# Shutdown_Nodes.net
KiCad netlist of a schematic drawn in Altium Designer
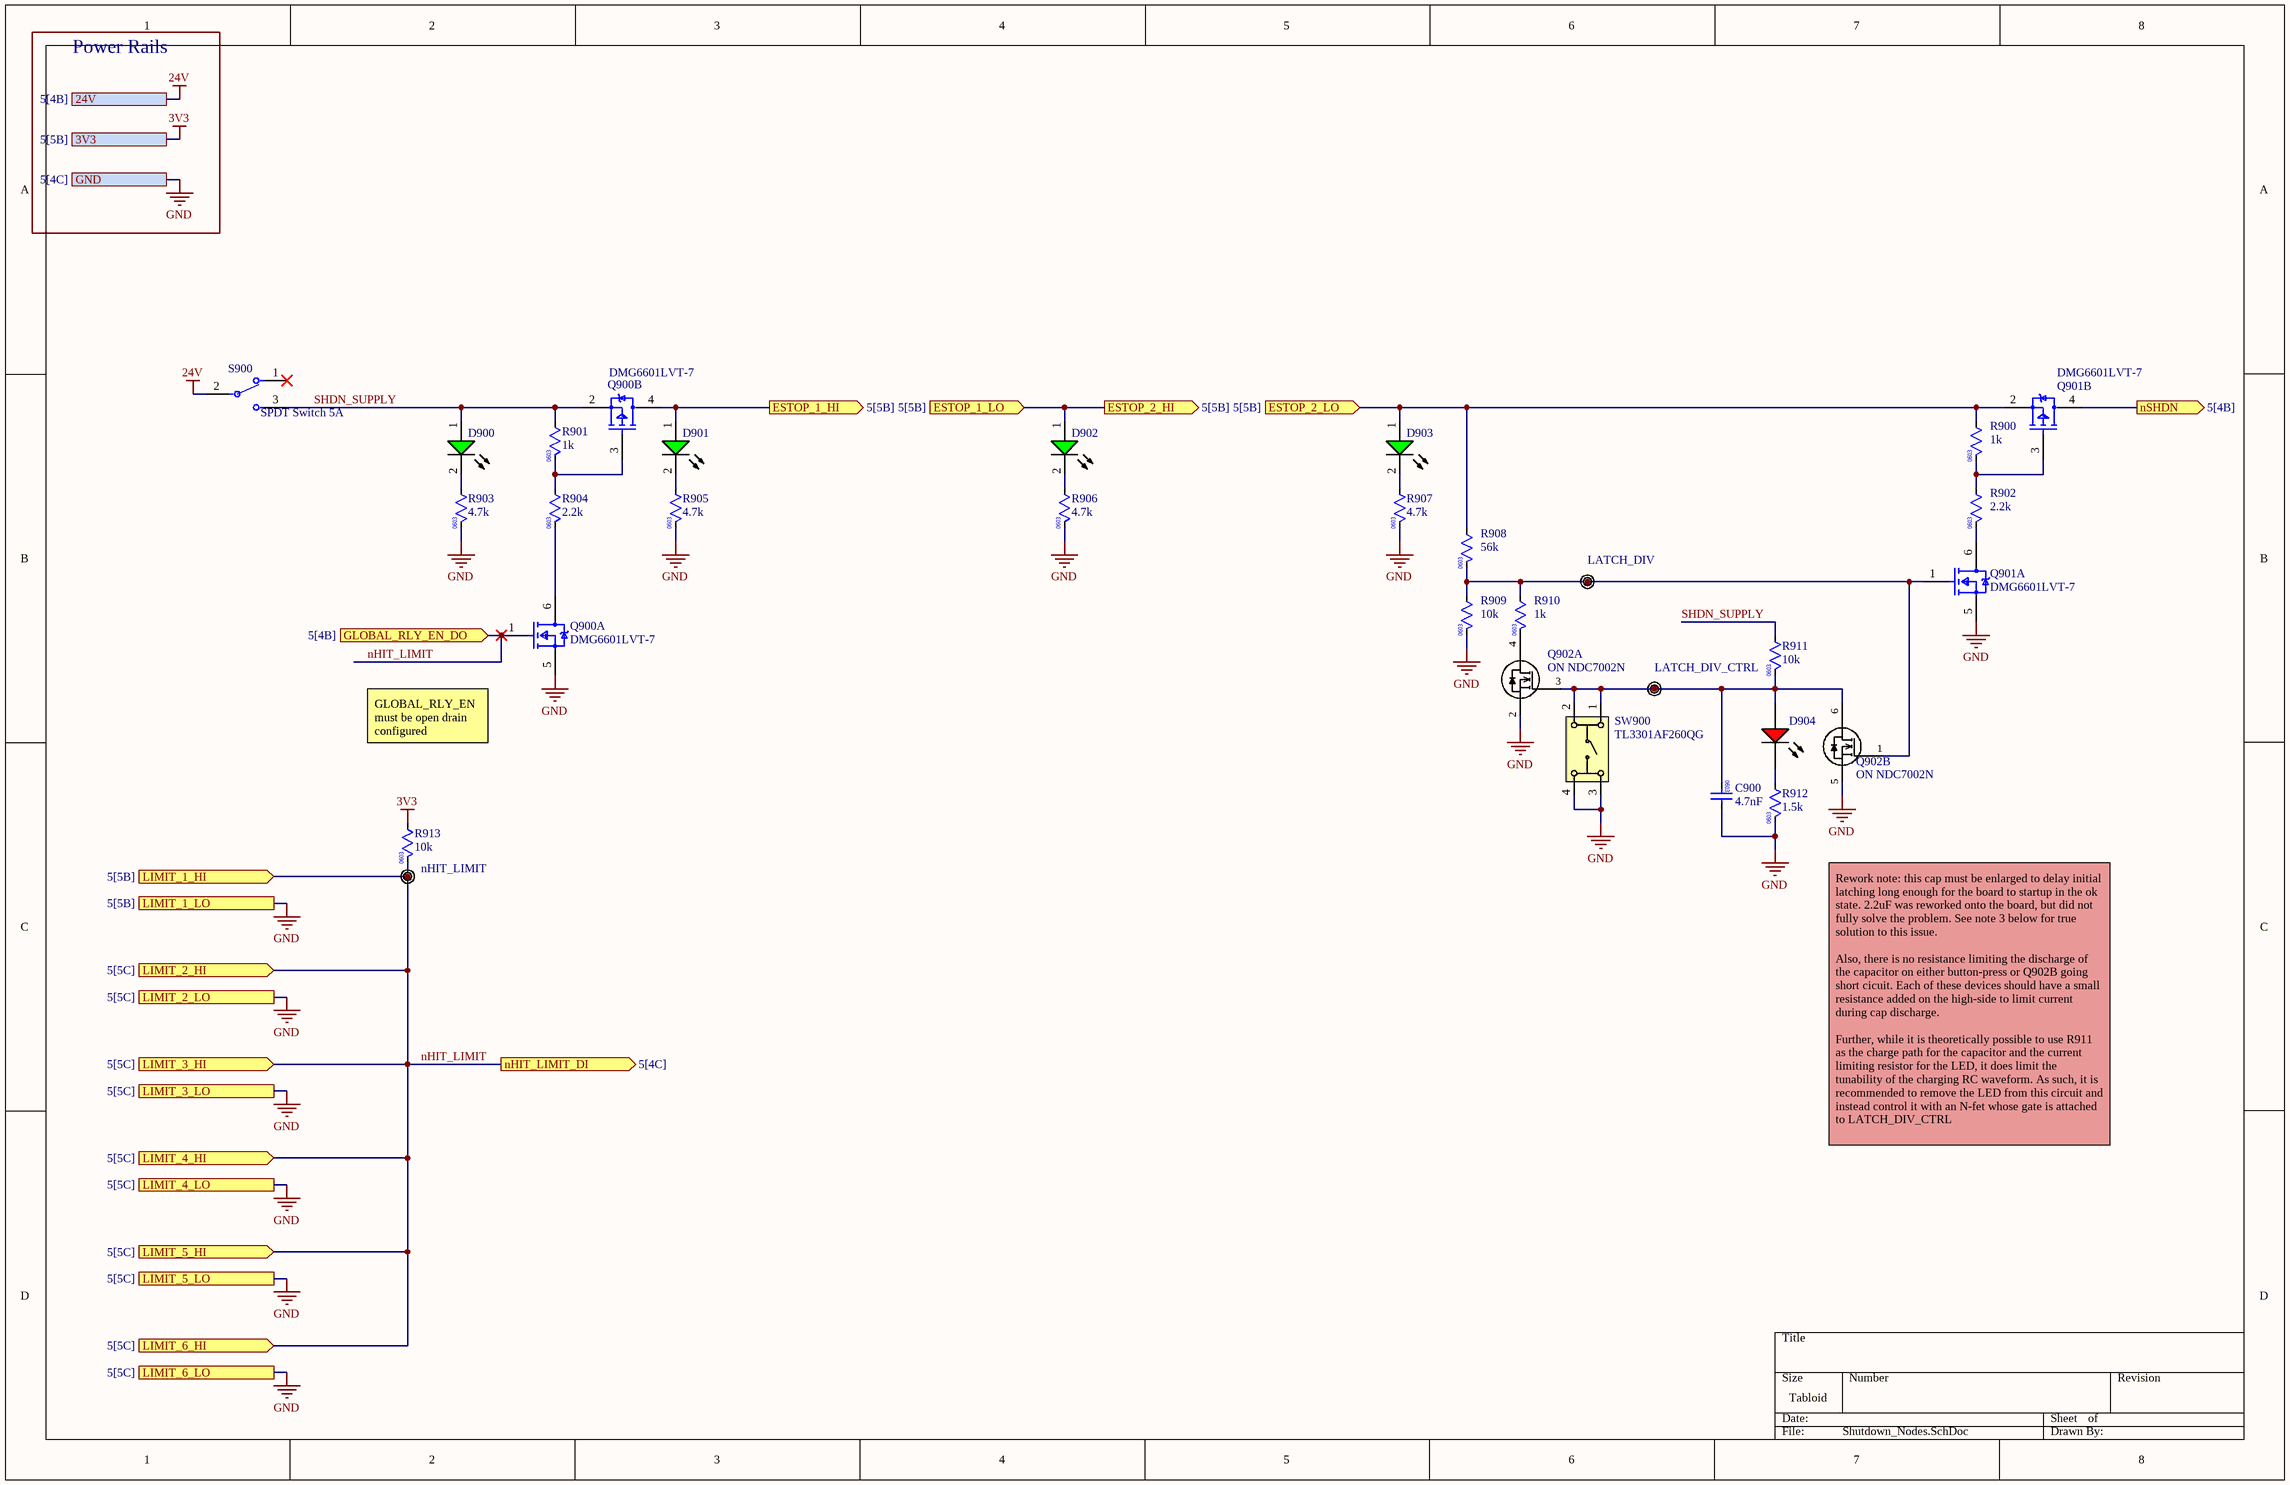
[diagram p0: Shutdown_Nodes.SchDoc]

(export (version "E")
  (design (tool "Eeschema 10.0.6"))
  (components
    (comp (ref "C900")
      (value "4.7nF")
      (footprint "0603 Capacitor Footprint")
      (description "Ceramic Capacitor, Multilayer, Ceramic, 50V, 10% Tol, X7R, 15% TC, 0.0047uF, Surface Mount, 0603")
      (fields
        (field (name "TOLERANCE") "10%")
        (field (name "Comment") "0603 4.7nF 10% 50V")
        (field (name "SOURCE") "UBC Formula Electric.SchLib")
      )
      (libsource (lib "UBC Formula Electric") (part "0603 Generic Ceramic Capacitor"))
    )
    (comp (ref "D900")
      (value "Lite-On LTST-C193KGKT-5A")
      (footprint "Lite-On LTST-C193KGKT-5A GREEN (1608)")
      (description "LED GREEN CLEAR CHIP SMD")
      (fields (field (name "SOURCE") "UBC Formula Electric.SchLib"))
      (libsource (lib "UBC Formula Electric") (part "Lite-On LTST-C193KGKT-5A"))
    )
    (comp (ref "D901")
      (value "Lite-On LTST-C193KGKT-5A")
      (footprint "Lite-On LTST-C193KGKT-5A GREEN (1608)")
      (description "LED GREEN CLEAR CHIP SMD")
      (fields (field (name "SOURCE") "UBC Formula Electric.SchLib"))
      (libsource (lib "UBC Formula Electric") (part "Lite-On LTST-C193KGKT-5A"))
    )
    (comp (ref "D902")
      (value "Lite-On LTST-C193KGKT-5A")
      (footprint "Lite-On LTST-C193KGKT-5A GREEN (1608)")
      (description "LED GREEN CLEAR CHIP SMD")
      (fields (field (name "SOURCE") "UBC Formula Electric.SchLib"))
      (libsource (lib "UBC Formula Electric") (part "Lite-On LTST-C193KGKT-5A"))
    )
    (comp (ref "D903")
      (value "Lite-On LTST-C193KGKT-5A")
      (footprint "Lite-On LTST-C193KGKT-5A GREEN (1608)")
      (description "LED GREEN CLEAR CHIP SMD")
      (fields (field (name "SOURCE") "UBC Formula Electric.SchLib"))
      (libsource (lib "UBC Formula Electric") (part "Lite-On LTST-C193KGKT-5A"))
    )
    (comp (ref "D904")
      (value "LTST-C190KRKT")
      (footprint "LTST-C191KRKT_V")
      (description "LED Uni-Color Red, 62.5 mW, 25 mA, -30 to 85 degC, 2-Pin SMD, RoHS, Tape and Reel")
      (fields (field (name "POWER") "75mW") (field (name "MANUFACTURER") "Lite-On"))
      (libsource (lib "UBC Formula Electric") (part "LED-RED-AK-2"))
    )
    (comp (ref "Q900")
      (value "DMG6601LVT-7")
      (footprint "FP-TSOT26-IPC_A")
      (libsource (lib "UBC Formula Electric") (part "06fe37a93ab8884fb11e636f76dd7e0"))
    )
    (comp (ref "Q901")
      (value "DMG6601LVT-7")
      (footprint "FP-TSOT26-IPC_A")
      (libsource (lib "UBC Formula Electric") (part "06fe37a93ab8884fb11e636f76dd7e0"))
    )
    (comp (ref "Q902")
      (value "ON NDC7002N")
      (footprint "SOT-6")
      (description "MOSFET 2N-CH 50V 0.51A SSOT6")
      (fields
        (field (name "MANUFACTURER") "ON Semiconductor / Fairchild")
        (field (name "MANUFACTURER PART NUMBER") "NDC7002N")
        (field (name "SOURCE") "UBC Formula Electric.SchLib")
      )
      (libsource (lib "") (part "ON NDC7002N_1"))
    )
    (comp (ref "R900")
      (value "1k")
      (footprint "0603 Resistor Footprint")
      (description "RES SMD 1K OHM 1% 1/3W 0603")
      (fields (field (name "TOLERANCE") "1%") (field (name "POWER") "250mW"))
      (libsource (lib "UBC Formula Electric") (part "RES-2"))
    )
    (comp (ref "R901")
      (value "1k")
      (footprint "0603 Resistor Footprint")
      (description "RES SMD 1K OHM 1% 1/3W 0603")
      (fields (field (name "TOLERANCE") "1%") (field (name "POWER") "250mW"))
      (libsource (lib "UBC Formula Electric") (part "RES-2"))
    )
    (comp (ref "R902")
      (value "2.2k")
      (footprint "0603 Resistor Footprint")
      (description "RES SMD 2.2K OHM 1% 1/4W 0603")
      (fields
        (field (name "DIGIKEY PART NUMBER") "541-10449-1-ND")
        (field (name "MANUFACTURER PART NUMBER") "RCS06032K20FKEA")
      )
      (libsource (lib "UBC Formula Electric") (part "RES-2"))
    )
    (comp (ref "R903")
      (value "4.7k")
      (footprint "0603 Resistor Footprint")
      (description "RES SMD 4.7K OHM 1% 1/3W 0603")
      (fields (field (name "TOLERANCE") "1%") (field (name "POWER") "250mW"))
      (libsource (lib "UBC Formula Electric") (part "RES-2"))
    )
    (comp (ref "R904")
      (value "2.2k")
      (footprint "0603 Resistor Footprint")
      (description "RES SMD 2.2K OHM 1% 1/4W 0603")
      (fields
        (field (name "DIGIKEY PART NUMBER") "541-10449-1-ND")
        (field (name "MANUFACTURER PART NUMBER") "RCS06032K20FKEA")
      )
      (libsource (lib "UBC Formula Electric") (part "RES-2"))
    )
    (comp (ref "R905")
      (value "4.7k")
      (footprint "0603 Resistor Footprint")
      (description "RES SMD 4.7K OHM 1% 1/3W 0603")
      (fields (field (name "TOLERANCE") "1%") (field (name "POWER") "250mW"))
      (libsource (lib "UBC Formula Electric") (part "RES-2"))
    )
    (comp (ref "R906")
      (value "4.7k")
      (footprint "0603 Resistor Footprint")
      (description "RES SMD 4.7K OHM 1% 1/3W 0603")
      (fields (field (name "TOLERANCE") "1%") (field (name "POWER") "250mW"))
      (libsource (lib "UBC Formula Electric") (part "RES-2"))
    )
    (comp (ref "R907")
      (value "4.7k")
      (footprint "0603 Resistor Footprint")
      (description "RES SMD 4.7K OHM 1% 1/3W 0603")
      (fields (field (name "TOLERANCE") "1%") (field (name "POWER") "250mW"))
      (libsource (lib "UBC Formula Electric") (part "RES-2"))
    )
    (comp (ref "R908")
      (value "56k")
      (footprint "0603 Resistor Footprint")
      (description "RES SMD 56K OHM 1% 1/3W 0603")
      (fields (field (name "TOLERANCE") "1%") (field (name "POWER") "333mW"))
      (libsource (lib "UBC Formula Electric") (part "RES-2"))
    )
    (comp (ref "R909")
      (value "10k")
      (footprint "0603 Resistor Footprint")
      (description "RES SMD 10K OHM 1% 1/3W 0603")
      (fields
        (field (name "MANUFACTURER PART NUMBER") "CRCW060310K0FKEAHP")
        (field (name "DIGIKEY PART NUMBER") "541-10.0KSCT-ND")
      )
      (libsource (lib "UBC Formula Electric") (part "RES-2"))
    )
    (comp (ref "R910")
      (value "1k")
      (footprint "0603 Resistor Footprint")
      (description "RES SMD 1K OHM 1% 1/3W 0603")
      (fields (field (name "POWER") "250mW") (field (name "TOLERANCE") "1%"))
      (libsource (lib "UBC Formula Electric") (part "RES-2"))
    )
    (comp (ref "R911")
      (value "10k")
      (footprint "0603 Resistor Footprint")
      (description "RES SMD 10K OHM 1% 1/3W 0603")
      (fields
        (field (name "MANUFACTURER PART NUMBER") "CRCW060310K0FKEAHP")
        (field (name "DIGIKEY PART NUMBER") "541-10.0KSCT-ND")
      )
      (libsource (lib "UBC Formula Electric") (part "RES-2"))
    )
    (comp (ref "R912")
      (value "1.5k")
      (footprint "0603 Resistor Footprint")
      (description "Res Thick Film 0603 1.5K Ohm 5% 0.25W(1/4W) ±200ppm/C Pad SMD Automotive T/R")
      (fields (field (name "POWER") "250mW") (field (name "TOLERANCE") "5%"))
      (libsource (lib "UBC Formula Electric") (part "RES-2"))
    )
    (comp (ref "R913")
      (value "10k")
      (footprint "0603 Resistor Footprint")
      (description "RES SMD 10K OHM 1% 1/3W 0603")
      (fields (field (name "TOLERANCE") "1%") (field (name "POWER") "333mW"))
      (libsource (lib "UBC Formula Electric") (part "RES-2"))
    )
    (comp (ref "S900")
      (value "SPDT Switch 5A")
      (footprint "SPDT 5A")
      (libsource (lib "air_hockey_lib") (part "SPDT Switch 5A"))
    )
    (comp (ref "SW900")
      (value "TL3301AF260QG")
      (footprint "MCU Reset Switch")
      (description "SWITCH TACTILE SPST-NO 0.05A 12V")
      (fields (field (name "SOURCE") "UBC Formula Electric.SchLib"))
      (libsource (lib "UBC Formula Electric") (part "E-Switch TL3301AF260QG"))
    )
    (comp (ref "TP900")
      (value "LATCH_DIV")
      (footprint "TESTPOINT")
      (fields (field (name "SOURCE") "UBC Formula Electric.SchLib"))
      (libsource (lib "UBC Formula Electric") (part "Thru-Hole Test Point"))
    )
    (comp (ref "TP901")
      (value "LATCH_DIV_CTRL")
      (footprint "TESTPOINT")
      (fields (field (name "SOURCE") "UBC Formula Electric.SchLib"))
      (libsource (lib "UBC Formula Electric") (part "Thru-Hole Test Point"))
    )
    (comp (ref "TP902")
      (value "nHIT_LIMIT")
      (footprint "TESTPOINT")
      (fields (field (name "SOURCE") "UBC Formula Electric.SchLib"))
      (libsource (lib "UBC Formula Electric") (part "Thru-Hole Test Point"))
    )
  )
  (nets
    (net (code "1") (name "/ESTOP_1_HI") (class "Default")
      (node (ref "D901") (pin "1") (pinfunction "A_1") (pintype "passive"))
      (node (ref "Q900") (pin "4") (pinfunction "D2_4") (pintype "passive"))
    )
    (net (code "2") (name "/ESTOP_1_LO") (class "Default")
      (node (ref "D902") (pin "1") (pinfunction "A_1") (pintype "passive"))
    )
    (net (code "3") (name "/ESTOP_2_LO") (class "Default")
      (node (ref "D903") (pin "1") (pinfunction "A_1") (pintype "passive"))
      (node (ref "Q901") (pin "2") (pinfunction "S2_2") (pintype "passive"))
      (node (ref "R900") (pin "1") (pinfunction "1_1") (pintype "passive"))
      (node (ref "R908") (pin "1") (pinfunction "1_1") (pintype "passive"))
    )
    (net (code "4") (name "/SHDN_SUPPLY") (class "Default")
      (node (ref "D900") (pin "1") (pinfunction "A_1") (pintype "passive"))
      (node (ref "Q900") (pin "2") (pinfunction "S2_2") (pintype "passive"))
      (node (ref "R901") (pin "1") (pinfunction "1_1") (pintype "passive"))
      (node (ref "R911") (pin "1") (pinfunction "1_1") (pintype "passive"))
      (node (ref "S900") (pin "3") (pinfunction "3_3") (pintype "passive"))
    )
    (net (code "5") (name "/nHIT_LIMIT") (class "Default")
      (node (ref "Q900") (pin "1") (pinfunction "G1_1") (pintype "passive"))
      (node (ref "R913") (pin "2") (pinfunction "2_2") (pintype "passive"))
      (node (ref "TP902") (pin "1") (pinfunction "TP_1") (pintype "passive"))
    )
    (net (code "6") (name "/nSHDN") (class "Default")
      (node (ref "Q901") (pin "4") (pinfunction "D2_4") (pintype "passive"))
    )
    (net (code "7") (name "3V3") (class "Default")
      (node (ref "R913") (pin "1") (pinfunction "1_1") (pintype "passive"))
    )
    (net (code "8") (name "24V") (class "Default")
      (node (ref "S900") (pin "2") (pinfunction "2_2") (pintype "passive"))
    )
    (net (code "9") (name "GND") (class "Default")
      (node (ref "C900") (pin "1") (pinfunction "1_1") (pintype "passive"))
      (node (ref "Q900") (pin "5") (pinfunction "S1_5") (pintype "passive"))
      (node (ref "Q901") (pin "5") (pinfunction "S1_5") (pintype "passive"))
      (node (ref "Q902") (pin "2") (pinfunction "SOURCE1_2") (pintype "passive"))
      (node (ref "Q902") (pin "5") (pinfunction "SOURCE2_5") (pintype "passive"))
      (node (ref "R903") (pin "2") (pinfunction "2_2") (pintype "passive"))
      (node (ref "R905") (pin "2") (pinfunction "2_2") (pintype "passive"))
      (node (ref "R906") (pin "2") (pinfunction "2_2") (pintype "passive"))
      (node (ref "R907") (pin "2") (pinfunction "2_2") (pintype "passive"))
      (node (ref "R909") (pin "2") (pinfunction "2_2") (pintype "passive"))
      (node (ref "R912") (pin "2") (pinfunction "2_2") (pintype "passive"))
      (node (ref "SW900") (pin "3") (pinfunction "3_3") (pintype "passive"))
      (node (ref "SW900") (pin "4") (pinfunction "4_4") (pintype "passive"))
    )
    (net (code "10") (name "Net-(D900-K)") (class "Default")
      (node (ref "D900") (pin "2") (pinfunction "K_2") (pintype "passive"))
      (node (ref "R903") (pin "1") (pinfunction "1_1") (pintype "passive"))
    )
    (net (code "11") (name "Net-(D901-K)") (class "Default")
      (node (ref "D901") (pin "2") (pinfunction "K_2") (pintype "passive"))
      (node (ref "R905") (pin "1") (pinfunction "1_1") (pintype "passive"))
    )
    (net (code "12") (name "Net-(D902-K)") (class "Default")
      (node (ref "D902") (pin "2") (pinfunction "K_2") (pintype "passive"))
      (node (ref "R906") (pin "1") (pinfunction "1_1") (pintype "passive"))
    )
    (net (code "13") (name "Net-(D903-K)") (class "Default")
      (node (ref "D903") (pin "2") (pinfunction "K_2") (pintype "passive"))
      (node (ref "R907") (pin "1") (pinfunction "1_1") (pintype "passive"))
    )
    (net (code "14") (name "Net-(D904-A)") (class "Default")
      (node (ref "C900") (pin "2") (pinfunction "2_2") (pintype "passive"))
      (node (ref "D904") (pin "1") (pinfunction "A_1") (pintype "passive"))
      (node (ref "Q902") (pin "3") (pinfunction "GATE1_3") (pintype "passive"))
      (node (ref "Q902") (pin "6") (pinfunction "DRAIN2_6") (pintype "passive"))
      (node (ref "R911") (pin "2") (pinfunction "2_2") (pintype "passive"))
      (node (ref "SW900") (pin "1") (pinfunction "1_1") (pintype "passive"))
      (node (ref "SW900") (pin "2") (pinfunction "2_2") (pintype "passive"))
      (node (ref "TP901") (pin "1") (pinfunction "TP_1") (pintype "passive"))
    )
    (net (code "15") (name "Net-(D904-K)") (class "Default")
      (node (ref "D904") (pin "2") (pinfunction "K_2") (pintype "passive"))
      (node (ref "R912") (pin "1") (pinfunction "1_1") (pintype "passive"))
    )
    (net (code "16") (name "Net-(Q900A-D1)") (class "Default")
      (node (ref "Q900") (pin "6") (pinfunction "D1_6") (pintype "passive"))
      (node (ref "R904") (pin "2") (pinfunction "2_2") (pintype "passive"))
    )
    (net (code "17") (name "Net-(Q900B-G2)") (class "Default")
      (node (ref "Q900") (pin "3") (pinfunction "G2_3") (pintype "passive"))
      (node (ref "R901") (pin "2") (pinfunction "2_2") (pintype "passive"))
      (node (ref "R904") (pin "1") (pinfunction "1_1") (pintype "passive"))
    )
    (net (code "18") (name "Net-(Q901A-D1)") (class "Default")
      (node (ref "Q901") (pin "6") (pinfunction "D1_6") (pintype "passive"))
      (node (ref "R902") (pin "2") (pinfunction "2_2") (pintype "passive"))
    )
    (net (code "19") (name "Net-(Q901A-G1)") (class "Default")
      (node (ref "Q901") (pin "1") (pinfunction "G1_1") (pintype "passive"))
      (node (ref "Q902") (pin "1") (pinfunction "GATE2_1") (pintype "passive"))
      (node (ref "R908") (pin "2") (pinfunction "2_2") (pintype "passive"))
      (node (ref "R909") (pin "1") (pinfunction "1_1") (pintype "passive"))
      (node (ref "R910") (pin "1") (pinfunction "1_1") (pintype "passive"))
      (node (ref "TP900") (pin "1") (pinfunction "TP_1") (pintype "passive"))
    )
    (net (code "20") (name "Net-(Q901B-G2)") (class "Default")
      (node (ref "Q901") (pin "3") (pinfunction "G2_3") (pintype "passive"))
      (node (ref "R900") (pin "2") (pinfunction "2_2") (pintype "passive"))
      (node (ref "R902") (pin "1") (pinfunction "1_1") (pintype "passive"))
    )
    (net (code "21") (name "Net-(Q902A-DRAIN1)") (class "Default")
      (node (ref "Q902") (pin "4") (pinfunction "DRAIN1_4") (pintype "passive"))
      (node (ref "R910") (pin "2") (pinfunction "2_2") (pintype "passive"))
    )
    (net (code "22") (name "unconnected-(S900-Pad1)") (class "Default")
      (node (ref "S900") (pin "1") (pinfunction "1_1") (pintype "passive+no_connect"))
    )
  )
)
